# Yukari4_Naninator.net
KiCad netlist of a schematic drawn in EAGLE
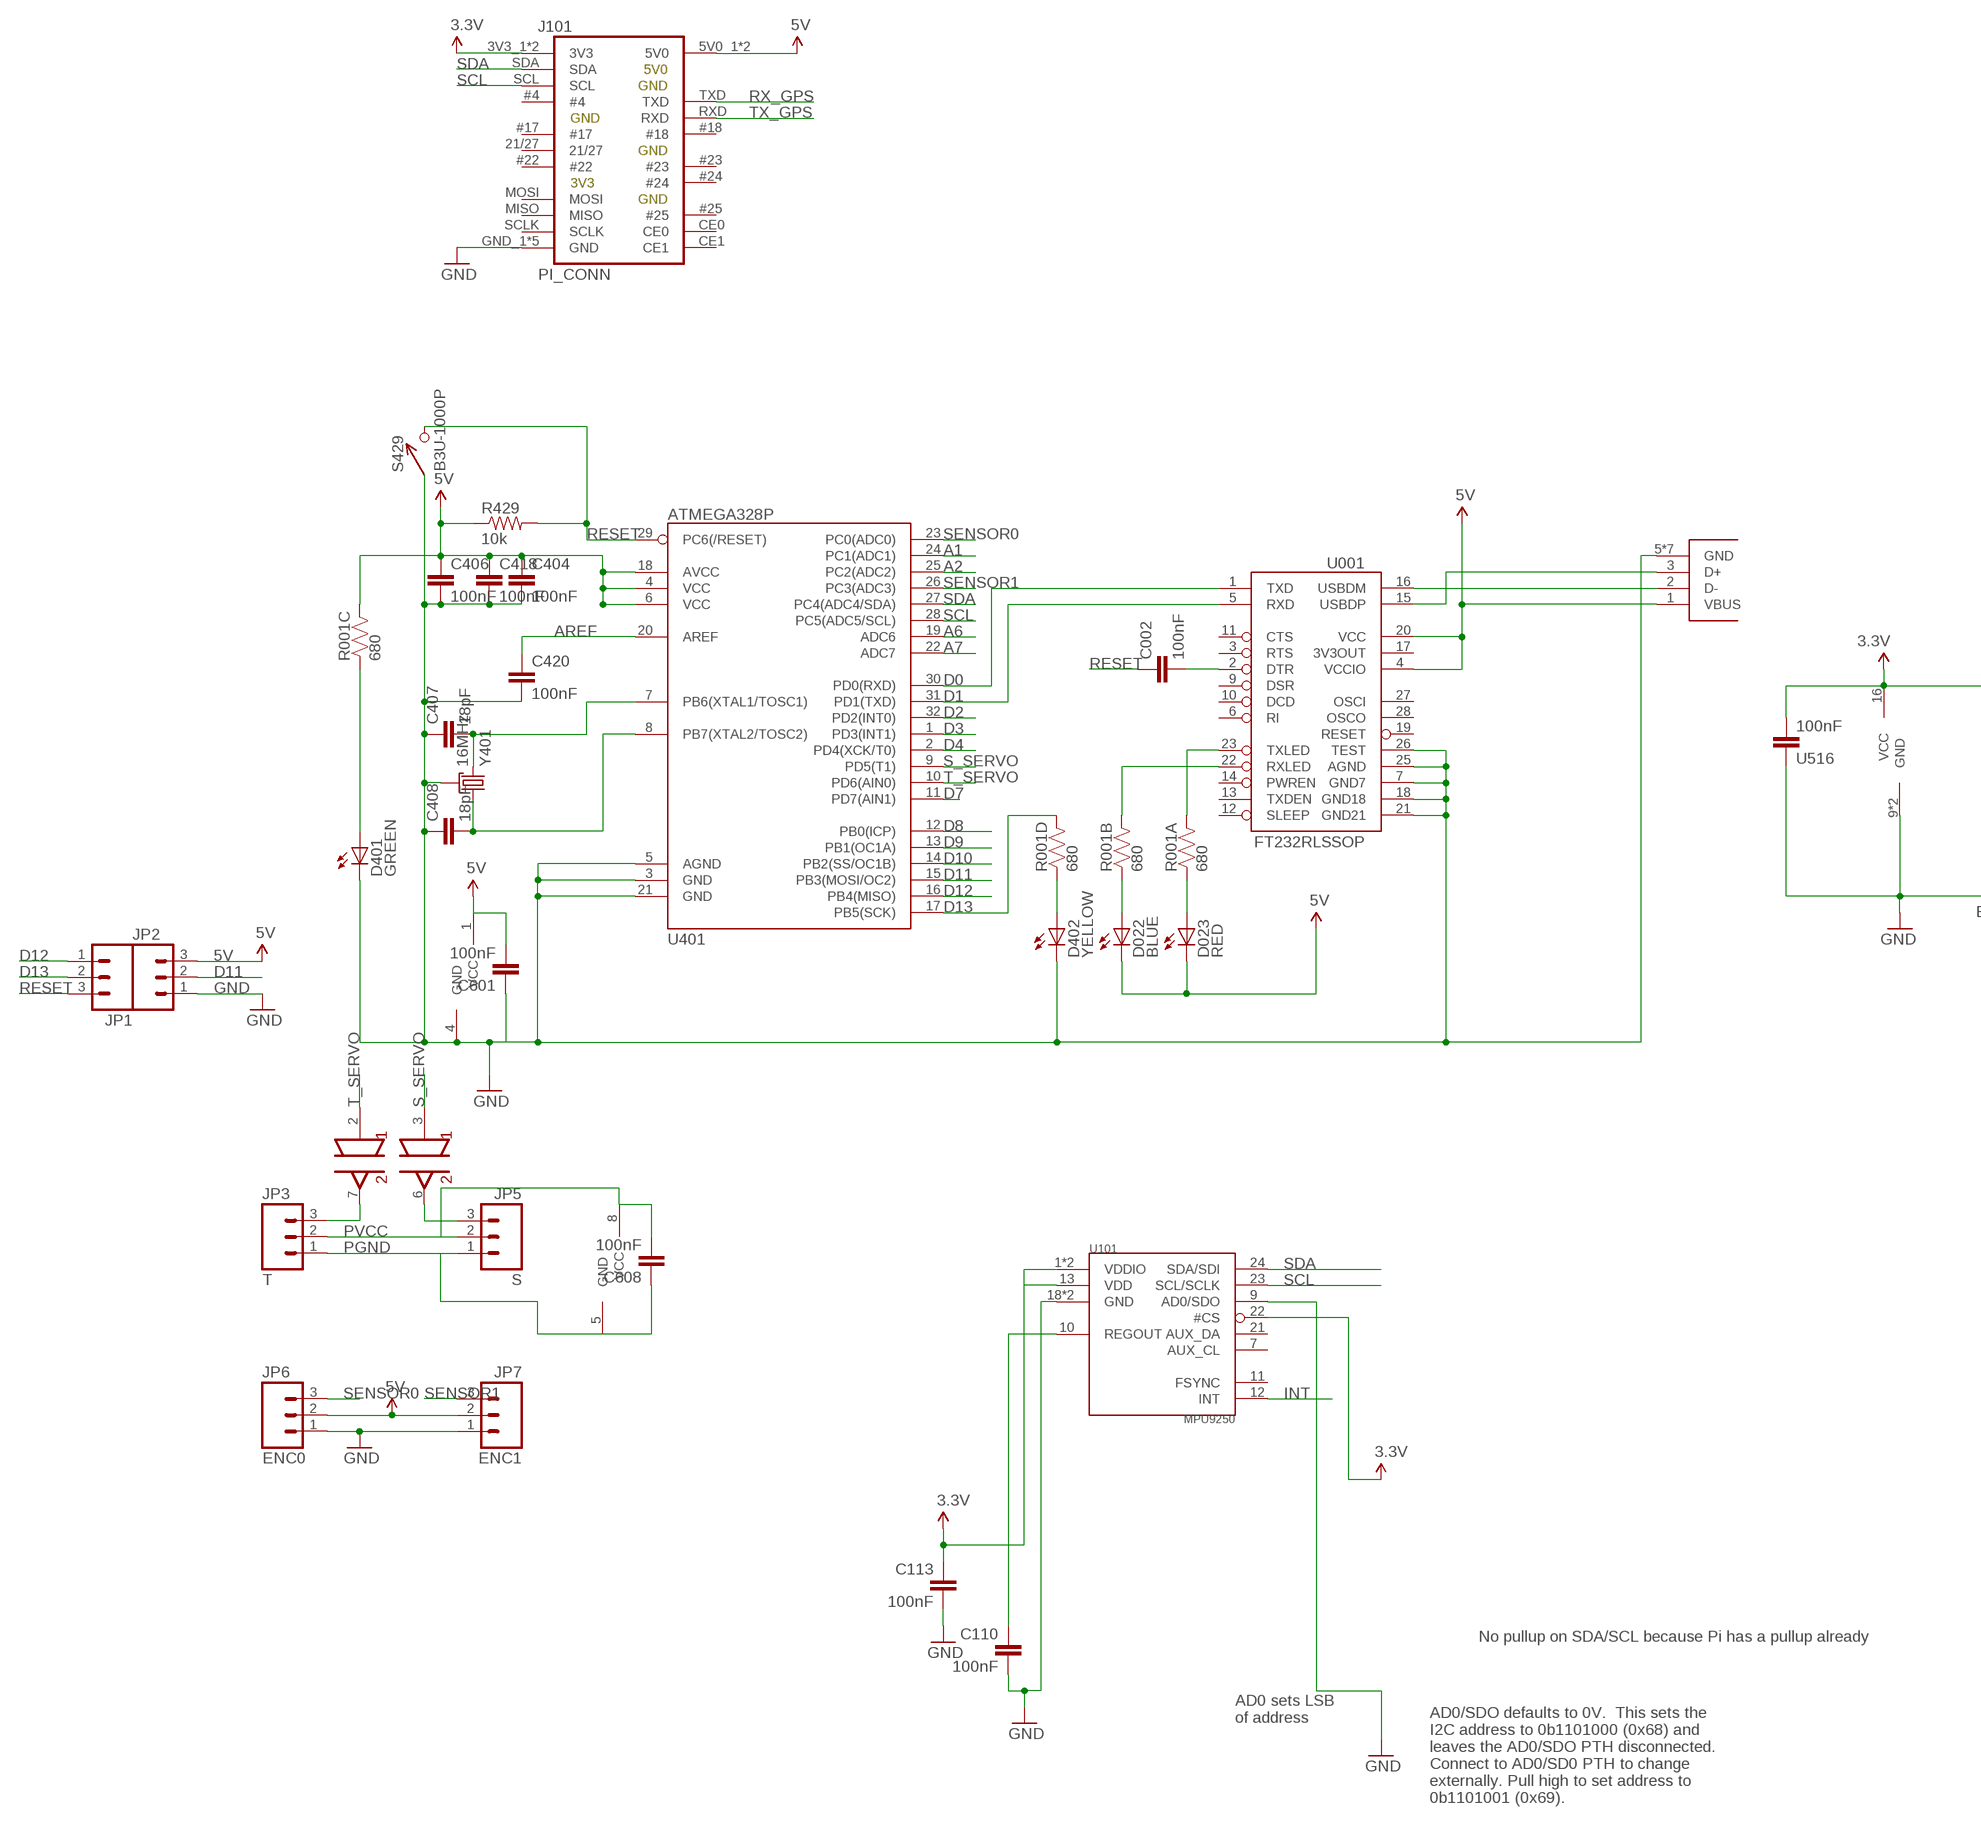
[diagram p0: schematic, sheet 1, part 1 of 2]
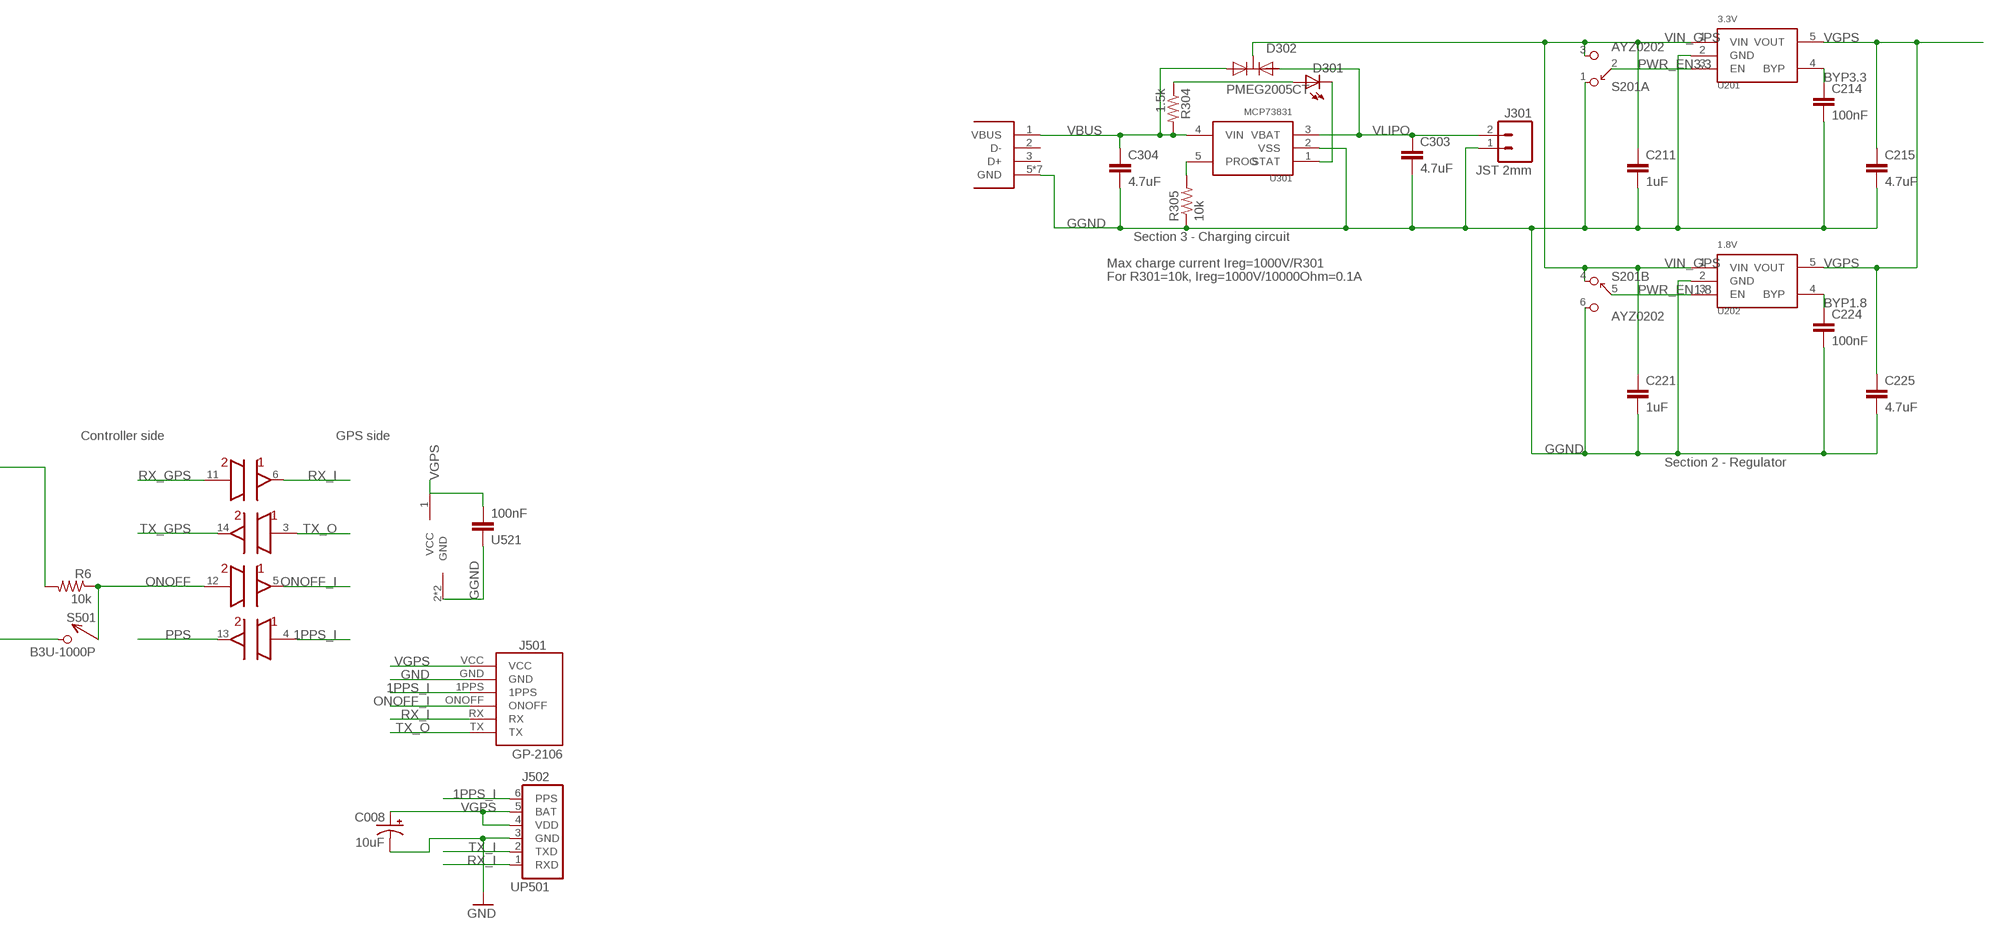
[diagram p1: schematic, sheet 1, part 2 of 2]

(export (version "E")
  (design (tool "Eeschema 10.0.6"))
  (components
    (comp (ref "C002")
      (value "100nF")
      (footprint "eagle-import:0402-CAP")
      (libsource (lib "eagle-import") (part "CAP0402-CAP"))
    )
    (comp (ref "C008")
      (value "10uF")
      (footprint "eagle-import:EIA3216")
      (libsource (lib "eagle-import") (part "CAP_POL1206"))
    )
    (comp (ref "C110")
      (value "100nF")
      (footprint "eagle-import:0402-CAP")
      (libsource (lib "eagle-import") (part "SparkFun-Capacitors_CAP0402-CAP"))
    )
    (comp (ref "C113")
      (value "100nF")
      (footprint "eagle-import:0402-CAP")
      (libsource (lib "eagle-import") (part "SparkFun-Capacitors_CAP0402-CAP"))
    )
    (comp (ref "C211")
      (value "1uF")
      (footprint "eagle-import:0402-CAP")
      (libsource (lib "eagle-import") (part "CAP0402-CAP"))
    )
    (comp (ref "C214")
      (value "100nF")
      (footprint "eagle-import:0402-CAP")
      (libsource (lib "eagle-import") (part "CAP0402-CAP"))
    )
    (comp (ref "C215")
      (value "4.7uF")
      (footprint "eagle-import:0402-CAP")
      (libsource (lib "eagle-import") (part "CAP0402-CAP"))
    )
    (comp (ref "C221")
      (value "1uF")
      (footprint "eagle-import:0402-CAP")
      (libsource (lib "eagle-import") (part "CAP0402-CAP"))
    )
    (comp (ref "C224")
      (value "100nF")
      (footprint "eagle-import:0402-CAP")
      (libsource (lib "eagle-import") (part "CAP0402-CAP"))
    )
    (comp (ref "C225")
      (value "4.7uF")
      (footprint "eagle-import:0402-CAP")
      (libsource (lib "eagle-import") (part "CAP0402-CAP"))
    )
    (comp (ref "C303")
      (value "4.7uF")
      (footprint "eagle-import:0402-CAP")
      (libsource (lib "eagle-import") (part "CAP0402-CAP"))
    )
    (comp (ref "C304")
      (value "4.7uF")
      (footprint "eagle-import:0402-CAP")
      (libsource (lib "eagle-import") (part "CAP0402-CAP"))
    )
    (comp (ref "C404")
      (value "100nF")
      (footprint "eagle-import:0402-CAP")
      (libsource (lib "eagle-import") (part "CAP0402-CAP"))
    )
    (comp (ref "C406")
      (value "100nF")
      (footprint "eagle-import:0402-CAP")
      (libsource (lib "eagle-import") (part "CAP0402-CAP"))
    )
    (comp (ref "C407")
      (value "18pF")
      (footprint "eagle-import:0402-CAP")
      (libsource (lib "eagle-import") (part "CAP0402-CAP"))
    )
    (comp (ref "C408")
      (value "18pF")
      (footprint "eagle-import:0402-CAP")
      (libsource (lib "eagle-import") (part "CAP0402-CAP"))
    )
    (comp (ref "C418")
      (value "100nF")
      (footprint "eagle-import:0402-CAP")
      (libsource (lib "eagle-import") (part "CAP0402-CAP"))
    )
    (comp (ref "C420")
      (value "100nF")
      (footprint "eagle-import:0402-CAP")
      (libsource (lib "eagle-import") (part "CAP0402-CAP"))
    )
    (comp (ref "C601")
      (value "100nF")
      (footprint "eagle-import:0402-CAP")
      (libsource (lib "eagle-import") (part "CAP0402-CAP"))
    )
    (comp (ref "C608")
      (value "100nF")
      (footprint "eagle-import:0402-CAP")
      (libsource (lib "eagle-import") (part "CAP0402-CAP"))
    )
    (comp (ref "D022")
      (value "BLUE")
      (footprint "eagle-import:LED-0603")
      (libsource (lib "eagle-import") (part "SparkFun-LED_LED0603"))
    )
    (comp (ref "D023")
      (value "RED")
      (footprint "eagle-import:LED-0603")
      (libsource (lib "eagle-import") (part "SparkFun-LED_LED0603"))
    )
    (comp (ref "D301")
      (value "YELLOW")
      (footprint "eagle-import:LED-0603")
      (libsource (lib "eagle-import") (part "LED0603"))
    )
    (comp (ref "D302")
      (value "PMEG2005CT")
      (footprint "eagle-import:SOT-23-3")
      (libsource (lib "eagle-import") (part "DIODE_COMMON_CATHODEPMEG2005CT"))
    )
    (comp (ref "D401")
      (value "GREEN")
      (footprint "eagle-import:LED-0603")
      (libsource (lib "eagle-import") (part "SparkFun-LED_LED0603"))
    )
    (comp (ref "D402")
      (value "YELLOW")
      (footprint "eagle-import:LED-0603")
      (libsource (lib "eagle-import") (part "SparkFun-LED_LED0603"))
    )
    (comp (ref "J001")
      (value "USB_MICROB_JST")
      (footprint "eagle-import:UB-MC5BR3-SD204-4S")
      (libsource (lib "eagle-import") (part "USB_MICROB_JST"))
    )
    (comp (ref "J101")
      (value "PI_CONN")
      (footprint "eagle-import:PI_CONN")
      (libsource (lib "eagle-import") (part "PI_CONN"))
    )
    (comp (ref "J301")
      (value "JST 2mm")
      (footprint "eagle-import:JST-2-SMD")
      (libsource (lib "eagle-import") (part "M02-JST-2MM-SMT"))
    )
    (comp (ref "J302")
      (value "USB_MICROB_JST")
      (footprint "eagle-import:UB-MC5BR3-SD204-4S")
      (libsource (lib "eagle-import") (part "USB_MICROB_JST"))
    )
    (comp (ref "J501")
      (value "GP-2106")
      (footprint "eagle-import:GP-2106")
      (libsource (lib "eagle-import") (part "GP-2106"))
    )
    (comp (ref "J502")
      (value "UP501")
      (footprint "eagle-import:UP501")
      (libsource (lib "eagle-import") (part "UP501"))
    )
    (comp (ref "JP1")
      (value "M03PTH")
      (footprint "eagle-import:1X03")
      (libsource (lib "eagle-import") (part "M03PTH"))
    )
    (comp (ref "JP2")
      (value "M03PTH")
      (footprint "eagle-import:1X03")
      (libsource (lib "eagle-import") (part "M03PTH"))
    )
    (comp (ref "JP3")
      (value "T")
      (footprint "eagle-import:1X03")
      (libsource (lib "eagle-import") (part "M03PTH"))
    )
    (comp (ref "JP5")
      (value "S")
      (footprint "eagle-import:1X03")
      (libsource (lib "eagle-import") (part "M03PTH"))
    )
    (comp (ref "JP6")
      (value "ENC0")
      (footprint "eagle-import:1X03")
      (libsource (lib "eagle-import") (part "M03PTH"))
    )
    (comp (ref "JP7")
      (value "ENC1")
      (footprint "eagle-import:1X03")
      (libsource (lib "eagle-import") (part "M03PTH"))
    )
    (comp (ref "R001")
      (value "680")
      (footprint "eagle-import:CRA04")
      (fields (field (name "DIGIKEY") "CRA4S8680CT-ND"))
      (libsource (lib "eagle-import") (part "RP404"))
    )
    (comp (ref "R6")
      (value "10k")
      (footprint "eagle-import:0402-RES")
      (libsource (lib "eagle-import") (part "RESISTOR0402-RES"))
    )
    (comp (ref "R304")
      (value "1.5k")
      (footprint "eagle-import:0402-RES")
      (libsource (lib "eagle-import") (part "RESISTOR0402-RES"))
    )
    (comp (ref "R305")
      (value "10k")
      (footprint "eagle-import:0402-RES")
      (libsource (lib "eagle-import") (part "RESISTOR0402-RES"))
    )
    (comp (ref "R429")
      (value "10k")
      (footprint "eagle-import:0402-RES")
      (libsource (lib "eagle-import") (part "SparkFun-Passives_RESISTOR0402-RES"))
    )
    (comp (ref "S201")
      (value "AYZ0202")
      (footprint "eagle-import:AYZ0202")
      (libsource (lib "eagle-import") (part "AYZ0202"))
    )
    (comp (ref "S429")
      (value "B3U-1000P")
      (footprint "eagle-import:B3U-1000P")
      (libsource (lib "eagle-import") (part "B3U-1000P"))
    )
    (comp (ref "S501")
      (value "B3U-1000P")
      (footprint "eagle-import:B3U-1000P")
      (libsource (lib "eagle-import") (part "B3U-1000P"))
    )
    (comp (ref "U001")
      (value "FT232RLSSOP")
      (footprint "eagle-import:SSOP28DB")
      (libsource (lib "eagle-import") (part "FT232RLSSOP"))
    )
    (comp (ref "U101")
      (value "MPU9250")
      (footprint "eagle-import:LQFN_3MM_3MM")
      (libsource (lib "eagle-import") (part "MPU9250"))
    )
    (comp (ref "U201")
      (value "3.3V")
      (footprint "eagle-import:SOT-23-5")
      (libsource (lib "eagle-import") (part "MIC5319D5"))
    )
    (comp (ref "U202")
      (value "1.8V")
      (footprint "eagle-import:SOT-23-5")
      (libsource (lib "eagle-import") (part "MIC5319D5"))
    )
    (comp (ref "U301")
      (value "MCP73831")
      (footprint "eagle-import:SOT-23-5")
      (libsource (lib "eagle-import") (part "MCP73831"))
    )
    (comp (ref "U401")
      (value "ATMEGA328P")
      (footprint "eagle-import:TQFP32-08")
      (libsource (lib "eagle-import") (part "ATMEGA168"))
    )
    (comp (ref "U501")
      (value "ADUM242E")
      (footprint "eagle-import:16-SOIC-W")
      (libsource (lib "eagle-import") (part "ADUM242E"))
    )
    (comp (ref "U516")
      (value "100nF")
      (footprint "eagle-import:0402-CAP")
      (libsource (lib "eagle-import") (part "CAP0402-CAP"))
    )
    (comp (ref "U521")
      (value "100nF")
      (footprint "eagle-import:0402-CAP")
      (libsource (lib "eagle-import") (part "CAP0402-CAP"))
    )
    (comp (ref "U601")
      (value "ADUM3221")
      (footprint "eagle-import:SO8N")
      (libsource (lib "eagle-import") (part "ADUM3221"))
    )
    (comp (ref "Y401")
      (value "16MHz")
      (footprint "eagle-import:CRYSTAL_SMD_2MM_2_5MM")
      (libsource (lib "eagle-import") (part "CX2520"))
    )
  )
  (nets
    (net (code "1") (name "/1PPS_I") (class "Default")
      (node (ref "J501") (pin "1PPS") (pinfunction "1PPS_1PPS") (pintype "bidirectional"))
      (node (ref "J502") (pin "6") (pinfunction "PPS_6") (pintype "passive"))
      (node (ref "U501") (pin "4") (pinfunction "IN_4") (pintype "input"))
    )
    (net (code "2") (name "/A1") (class "Default")
      (node (ref "U401") (pin "24") (pinfunction "PC1(ADC1)_24") (pintype "bidirectional"))
    )
    (net (code "3") (name "/A2") (class "Default")
      (node (ref "U401") (pin "25") (pinfunction "PC2(ADC2)_25") (pintype "bidirectional"))
    )
    (net (code "4") (name "/A6") (class "Default")
      (node (ref "U401") (pin "19") (pinfunction "ADC6_19") (pintype "bidirectional"))
    )
    (net (code "5") (name "/A7") (class "Default")
      (node (ref "U401") (pin "22") (pinfunction "ADC7_22") (pintype "bidirectional"))
    )
    (net (code "6") (name "/AREF") (class "Default")
      (node (ref "C420") (pin "1") (pinfunction "1_1") (pintype "passive"))
      (node (ref "U401") (pin "20") (pinfunction "AREF_20") (pintype "bidirectional"))
    )
    (net (code "7") (name "/BYP1.8") (class "Default")
      (node (ref "C224") (pin "1") (pinfunction "1_1") (pintype "passive"))
      (node (ref "U202") (pin "4") (pinfunction "BYP_4") (pintype "bidirectional"))
    )
    (net (code "8") (name "/BYP3.3") (class "Default")
      (node (ref "C214") (pin "1") (pinfunction "1_1") (pintype "passive"))
      (node (ref "U201") (pin "4") (pinfunction "BYP_4") (pintype "bidirectional"))
    )
    (net (code "9") (name "/D0") (class "Default")
      (node (ref "U001") (pin "1") (pinfunction "TXD_1") (pintype "output"))
      (node (ref "U401") (pin "30") (pinfunction "PD0(RXD)_30") (pintype "bidirectional"))
    )
    (net (code "10") (name "/D1") (class "Default")
      (node (ref "U001") (pin "5") (pinfunction "RXD_5") (pintype "input"))
      (node (ref "U401") (pin "31") (pinfunction "PD1(TXD)_31") (pintype "bidirectional"))
    )
    (net (code "11") (name "/D2") (class "Default")
      (node (ref "U401") (pin "32") (pinfunction "PD2(INT0)_32") (pintype "bidirectional"))
    )
    (net (code "12") (name "/D3") (class "Default")
      (node (ref "U401") (pin "1") (pinfunction "PD3(INT1)_1") (pintype "bidirectional"))
    )
    (net (code "13") (name "/D4") (class "Default")
      (node (ref "U401") (pin "2") (pinfunction "PD4(XCK/T0)_2") (pintype "bidirectional"))
    )
    (net (code "14") (name "/D7") (class "Default")
      (node (ref "U401") (pin "11") (pinfunction "PD7(AIN1)_11") (pintype "bidirectional"))
    )
    (net (code "15") (name "/D8") (class "Default")
      (node (ref "U401") (pin "12") (pinfunction "PB0(ICP)_12") (pintype "bidirectional"))
    )
    (net (code "16") (name "/D9") (class "Default")
      (node (ref "U401") (pin "13") (pinfunction "PB1(OC1A)_13") (pintype "bidirectional"))
    )
    (net (code "17") (name "/D10") (class "Default")
      (node (ref "U401") (pin "14") (pinfunction "PB2(SS/OC1B)_14") (pintype "bidirectional"))
    )
    (net (code "18") (name "/D11") (class "Default")
      (node (ref "JP2") (pin "2") (pinfunction "2_2") (pintype "passive"))
      (node (ref "U401") (pin "15") (pinfunction "PB3(MOSI/OC2)_15") (pintype "bidirectional"))
    )
    (net (code "19") (name "/D12") (class "Default")
      (node (ref "JP1") (pin "1") (pinfunction "1_1") (pintype "passive"))
      (node (ref "U401") (pin "16") (pinfunction "PB4(MISO)_16") (pintype "bidirectional"))
    )
    (net (code "20") (name "/D13") (class "Default")
      (node (ref "JP1") (pin "2") (pinfunction "2_2") (pintype "passive"))
      (node (ref "R001") (pin "5") (pinfunction "2_5") (pintype "passive"))
      (node (ref "U401") (pin "17") (pinfunction "PB5(SCK)_17") (pintype "bidirectional"))
    )
    (net (code "21") (name "/GGND") (class "Default")
      (node (ref "C211") (pin "2") (pinfunction "2_2") (pintype "passive"))
      (node (ref "C214") (pin "2") (pinfunction "2_2") (pintype "passive"))
      (node (ref "C215") (pin "2") (pinfunction "2_2") (pintype "passive"))
      (node (ref "C221") (pin "2") (pinfunction "2_2") (pintype "passive"))
      (node (ref "C224") (pin "2") (pinfunction "2_2") (pintype "passive"))
      (node (ref "C225") (pin "2") (pinfunction "2_2") (pintype "passive"))
      (node (ref "C303") (pin "2") (pinfunction "2_2") (pintype "passive"))
      (node (ref "C304") (pin "2") (pinfunction "2_2") (pintype "passive"))
      (node (ref "J301") (pin "1") (pinfunction "1_1") (pintype "passive"))
      (node (ref "J302") (pin "5") (pinfunction "GND_5") (pintype "bidirectional"))
      (node (ref "J302") (pin "P$10") (pinfunction "GND_P$10") (pintype "bidirectional"))
      (node (ref "J302") (pin "P$11") (pinfunction "GND_P$11") (pintype "bidirectional"))
      (node (ref "J302") (pin "P$6") (pinfunction "GND_P$6") (pintype "bidirectional"))
      (node (ref "J302") (pin "P$7") (pinfunction "GND_P$7") (pintype "bidirectional"))
      (node (ref "J302") (pin "P$8") (pinfunction "GND_P$8") (pintype "bidirectional"))
      (node (ref "J302") (pin "P$9") (pinfunction "GND_P$9") (pintype "bidirectional"))
      (node (ref "R305") (pin "1") (pinfunction "1_1") (pintype "passive"))
      (node (ref "S201") (pin "1") (pinfunction "P$1_1") (pintype "bidirectional"))
      (node (ref "S201") (pin "6") (pinfunction "P$2_6") (pintype "bidirectional"))
      (node (ref "U201") (pin "2") (pinfunction "GND_2") (pintype "bidirectional"))
      (node (ref "U202") (pin "2") (pinfunction "GND_2") (pintype "bidirectional"))
      (node (ref "U301") (pin "2") (pinfunction "VSS_2") (pintype "power_in"))
      (node (ref "U501") (pin "2") (pinfunction "GND_2") (pintype "bidirectional"))
      (node (ref "U501") (pin "8") (pinfunction "GND_8") (pintype "bidirectional"))
      (node (ref "U521") (pin "1") (pinfunction "1_1") (pintype "passive"))
    )
    (net (code "22") (name "/INT") (class "Default")
      (node (ref "U101") (pin "12") (pinfunction "INT_12") (pintype "bidirectional"))
    )
    (net (code "23") (name "/ONOFF") (class "Default")
      (node (ref "R6") (pin "1") (pinfunction "1_1") (pintype "passive"))
      (node (ref "S501") (pin "P$1") (pinfunction "1_P$1") (pintype "bidirectional"))
      (node (ref "U501") (pin "12") (pinfunction "IN_12") (pintype "input"))
    )
    (net (code "24") (name "/ONOFF_I") (class "Default")
      (node (ref "J501") (pin "ONOFF") (pinfunction "ONOFF_ONOFF") (pintype "bidirectional"))
      (node (ref "U501") (pin "5") (pinfunction "OUT_5") (pintype "bidirectional"))
    )
    (net (code "25") (name "/PGND") (class "Default")
      (node (ref "C608") (pin "1") (pinfunction "1_1") (pintype "passive"))
      (node (ref "JP3") (pin "1") (pinfunction "1_1") (pintype "passive"))
      (node (ref "JP5") (pin "1") (pinfunction "1_1") (pintype "passive"))
      (node (ref "U601") (pin "5") (pinfunction "GND_5") (pintype "bidirectional"))
    )
    (net (code "26") (name "/PPS") (class "Default")
      (node (ref "U501") (pin "13") (pinfunction "OUT_13") (pintype "bidirectional"))
    )
    (net (code "27") (name "/PVCC") (class "Default")
      (node (ref "C608") (pin "2") (pinfunction "2_2") (pintype "passive"))
      (node (ref "JP3") (pin "2") (pinfunction "2_2") (pintype "passive"))
      (node (ref "JP5") (pin "2") (pinfunction "2_2") (pintype "passive"))
      (node (ref "U601") (pin "8") (pinfunction "VCC_8") (pintype "bidirectional"))
    )
    (net (code "28") (name "/PWR_EN1.8") (class "Default")
      (node (ref "S201") (pin "5") (pinfunction "P$3_5") (pintype "bidirectional"))
      (node (ref "U202") (pin "3") (pinfunction "EN_3") (pintype "bidirectional"))
    )
    (net (code "29") (name "/PWR_EN3.3") (class "Default")
      (node (ref "S201") (pin "2") (pinfunction "P$3_2") (pintype "bidirectional"))
      (node (ref "U201") (pin "3") (pinfunction "EN_3") (pintype "bidirectional"))
    )
    (net (code "30") (name "/RESET") (class "Default")
      (node (ref "C002") (pin "1") (pinfunction "1_1") (pintype "passive"))
      (node (ref "JP1") (pin "3") (pinfunction "3_3") (pintype "passive"))
      (node (ref "R429") (pin "2") (pinfunction "2_2") (pintype "passive"))
      (node (ref "S429") (pin "P$2") (pinfunction "2_P$2") (pintype "bidirectional"))
      (node (ref "U401") (pin "29") (pinfunction "PC6(/RESET)_29") (pintype "bidirectional"))
    )
    (net (code "31") (name "/RX_GPS") (class "Default")
      (node (ref "J101") (pin "TXD") (pinfunction "TXD_TXD") (pintype "passive"))
      (node (ref "U501") (pin "11") (pinfunction "IN_11") (pintype "input"))
    )
    (net (code "32") (name "/RX_I") (class "Default")
      (node (ref "J501") (pin "RX") (pinfunction "RX_RX") (pintype "bidirectional"))
      (node (ref "J502") (pin "1") (pinfunction "RXD_1") (pintype "passive"))
      (node (ref "U501") (pin "6") (pinfunction "OUT_6") (pintype "bidirectional"))
    )
    (net (code "33") (name "/SCL") (class "Default")
      (node (ref "J101") (pin "SCL") (pinfunction "SCL_SCL") (pintype "passive"))
      (node (ref "U101") (pin "23") (pinfunction "SCL/SCLK_23") (pintype "bidirectional"))
      (node (ref "U401") (pin "28") (pinfunction "PC5(ADC5/SCL)_28") (pintype "bidirectional"))
    )
    (net (code "34") (name "/SDA") (class "Default")
      (node (ref "J101") (pin "SDA") (pinfunction "SDA_SDA") (pintype "passive"))
      (node (ref "U101") (pin "24") (pinfunction "SDA/SDI_24") (pintype "bidirectional"))
      (node (ref "U401") (pin "27") (pinfunction "PC4(ADC4/SDA)_27") (pintype "bidirectional"))
    )
    (net (code "35") (name "/SENSOR0") (class "Default")
      (node (ref "JP6") (pin "3") (pinfunction "3_3") (pintype "passive"))
      (node (ref "U401") (pin "23") (pinfunction "PC0(ADC0)_23") (pintype "bidirectional"))
    )
    (net (code "36") (name "/SENSOR1") (class "Default")
      (node (ref "JP7") (pin "3") (pinfunction "3_3") (pintype "passive"))
      (node (ref "U401") (pin "26") (pinfunction "PC3(ADC3)_26") (pintype "bidirectional"))
    )
    (net (code "37") (name "/S_SERVO") (class "Default")
      (node (ref "U401") (pin "9") (pinfunction "PD5(T1)_9") (pintype "bidirectional"))
      (node (ref "U601") (pin "3") (pinfunction "IN_3") (pintype "input"))
    )
    (net (code "38") (name "/TX_GPS") (class "Default")
      (node (ref "J101") (pin "RXD") (pinfunction "RXD_RXD") (pintype "passive"))
      (node (ref "U501") (pin "14") (pinfunction "OUT_14") (pintype "bidirectional"))
    )
    (net (code "39") (name "/TX_I") (class "Default")
      (node (ref "J502") (pin "2") (pinfunction "TXD_2") (pintype "passive"))
    )
    (net (code "40") (name "/TX_O") (class "Default")
      (node (ref "J501") (pin "TX") (pinfunction "TX_TX") (pintype "bidirectional"))
      (node (ref "U501") (pin "3") (pinfunction "IN_3") (pintype "input"))
    )
    (net (code "41") (name "/T_SERVO") (class "Default")
      (node (ref "U401") (pin "10") (pinfunction "PD6(AIN0)_10") (pintype "bidirectional"))
      (node (ref "U601") (pin "2") (pinfunction "IN_2") (pintype "input"))
    )
    (net (code "42") (name "/VBUS") (class "Default")
      (node (ref "C304") (pin "1") (pinfunction "1_1") (pintype "passive"))
      (node (ref "D302") (pin "1") (pinfunction "A1_1") (pintype "passive"))
      (node (ref "J302") (pin "1") (pinfunction "VBUS_1") (pintype "bidirectional"))
      (node (ref "R304") (pin "2") (pinfunction "2_2") (pintype "passive"))
      (node (ref "U301") (pin "4") (pinfunction "VIN_4") (pintype "power_in"))
    )
    (net (code "43") (name "/VGPS") (class "Default")
      (node (ref "C008") (pin "A") (pinfunction "+_A") (pintype "passive"))
      (node (ref "C215") (pin "1") (pinfunction "1_1") (pintype "passive"))
      (node (ref "C225") (pin "1") (pinfunction "1_1") (pintype "passive"))
      (node (ref "J501") (pin "VCC") (pinfunction "VCC_VCC") (pintype "bidirectional"))
      (node (ref "J502") (pin "4") (pinfunction "VDD_4") (pintype "passive"))
      (node (ref "J502") (pin "5") (pinfunction "BAT_5") (pintype "passive"))
      (node (ref "U201") (pin "5") (pinfunction "VOUT_5") (pintype "bidirectional"))
      (node (ref "U202") (pin "5") (pinfunction "VOUT_5") (pintype "bidirectional"))
      (node (ref "U501") (pin "1") (pinfunction "VCC_1") (pintype "bidirectional"))
      (node (ref "U521") (pin "2") (pinfunction "2_2") (pintype "passive"))
    )
    (net (code "44") (name "/VIN_GPS") (class "Default")
      (node (ref "C211") (pin "1") (pinfunction "1_1") (pintype "passive"))
      (node (ref "C221") (pin "1") (pinfunction "1_1") (pintype "passive"))
      (node (ref "D302") (pin "3") (pinfunction "K_3") (pintype "passive"))
      (node (ref "S201") (pin "3") (pinfunction "P$2_3") (pintype "bidirectional"))
      (node (ref "S201") (pin "4") (pinfunction "P$1_4") (pintype "bidirectional"))
      (node (ref "U201") (pin "1") (pinfunction "VIN_1") (pintype "bidirectional"))
      (node (ref "U202") (pin "1") (pinfunction "VIN_1") (pintype "bidirectional"))
    )
    (net (code "45") (name "/VLIPO") (class "Default")
      (node (ref "C303") (pin "1") (pinfunction "1_1") (pintype "passive"))
      (node (ref "D302") (pin "2") (pinfunction "A2_2") (pintype "passive"))
      (node (ref "J301") (pin "2") (pinfunction "2_2") (pintype "passive"))
      (node (ref "U301") (pin "3") (pinfunction "VBAT_3") (pintype "power_in"))
    )
    (net (code "46") (name "3.3V") (class "Default")
      (node (ref "C113") (pin "1") (pinfunction "1_1") (pintype "passive"))
      (node (ref "J101") (pin "3V3_1") (pinfunction "3V3_3V3_1") (pintype "passive"))
      (node (ref "J101") (pin "3V3_2") (pinfunction "3V3_3V3_2") (pintype "passive"))
      (node (ref "R6") (pin "2") (pinfunction "2_2") (pintype "passive"))
      (node (ref "U101") (pin "1") (pinfunction "VDDIO_1") (pintype "bidirectional"))
      (node (ref "U101") (pin "13") (pinfunction "VDD_13") (pintype "bidirectional"))
      (node (ref "U101") (pin "22") (pinfunction "#CS_22") (pintype "bidirectional"))
      (node (ref "U101") (pin "8") (pinfunction "VDDIO_8") (pintype "bidirectional"))
      (node (ref "U501") (pin "16") (pinfunction "VCC_16") (pintype "bidirectional"))
      (node (ref "U516") (pin "2") (pinfunction "2_2") (pintype "passive"))
    )
    (net (code "47") (name "5V") (class "Default")
      (node (ref "C404") (pin "1") (pinfunction "1_1") (pintype "passive"))
      (node (ref "C406") (pin "1") (pinfunction "1_1") (pintype "passive"))
      (node (ref "C418") (pin "1") (pinfunction "1_1") (pintype "passive"))
      (node (ref "C601") (pin "2") (pinfunction "2_2") (pintype "passive"))
      (node (ref "D022") (pin "C") (pinfunction "C_C") (pintype "passive"))
      (node (ref "D023") (pin "C") (pinfunction "C_C") (pintype "passive"))
      (node (ref "J001") (pin "1") (pinfunction "VBUS_1") (pintype "bidirectional"))
      (node (ref "J101") (pin "5V0_1") (pinfunction "5V0_5V0_1") (pintype "passive"))
      (node (ref "J101") (pin "5V0_2") (pinfunction "5V0_5V0_2") (pintype "passive"))
      (node (ref "JP2") (pin "3") (pinfunction "3_3") (pintype "passive"))
      (node (ref "JP6") (pin "2") (pinfunction "2_2") (pintype "passive"))
      (node (ref "JP7") (pin "2") (pinfunction "2_2") (pintype "passive"))
      (node (ref "R001") (pin "6") (pinfunction "2_6") (pintype "passive"))
      (node (ref "R429") (pin "1") (pinfunction "1_1") (pintype "passive"))
      (node (ref "U001") (pin "20") (pinfunction "VCC_20") (pintype "power_in"))
      (node (ref "U001") (pin "4") (pinfunction "VCCIO_4") (pintype "power_in"))
      (node (ref "U401") (pin "18") (pinfunction "AVCC_18") (pintype "bidirectional"))
      (node (ref "U401") (pin "4") (pinfunction "VCC_4") (pintype "bidirectional"))
      (node (ref "U401") (pin "6") (pinfunction "VCC_6") (pintype "bidirectional"))
      (node (ref "U601") (pin "1") (pinfunction "VCC_1") (pintype "bidirectional"))
    )
    (net (code "48") (name "GND") (class "Default")
      (node (ref "C008") (pin "C") (pinfunction "-_C") (pintype "passive"))
      (node (ref "C110") (pin "2") (pinfunction "2_2") (pintype "passive"))
      (node (ref "C113") (pin "2") (pinfunction "2_2") (pintype "passive"))
      (node (ref "C404") (pin "2") (pinfunction "2_2") (pintype "passive"))
      (node (ref "C406") (pin "2") (pinfunction "2_2") (pintype "passive"))
      (node (ref "C407") (pin "1") (pinfunction "1_1") (pintype "passive"))
      (node (ref "C408") (pin "1") (pinfunction "1_1") (pintype "passive"))
      (node (ref "C418") (pin "2") (pinfunction "2_2") (pintype "passive"))
      (node (ref "C420") (pin "2") (pinfunction "2_2") (pintype "passive"))
      (node (ref "C601") (pin "1") (pinfunction "1_1") (pintype "passive"))
      (node (ref "D401") (pin "C") (pinfunction "C_C") (pintype "passive"))
      (node (ref "D402") (pin "C") (pinfunction "C_C") (pintype "passive"))
      (node (ref "J001") (pin "5") (pinfunction "GND_5") (pintype "bidirectional"))
      (node (ref "J001") (pin "P$10") (pinfunction "GND_P$10") (pintype "bidirectional"))
      (node (ref "J001") (pin "P$11") (pinfunction "GND_P$11") (pintype "bidirectional"))
      (node (ref "J001") (pin "P$6") (pinfunction "GND_P$6") (pintype "bidirectional"))
      (node (ref "J001") (pin "P$7") (pinfunction "GND_P$7") (pintype "bidirectional"))
      (node (ref "J001") (pin "P$8") (pinfunction "GND_P$8") (pintype "bidirectional"))
      (node (ref "J001") (pin "P$9") (pinfunction "GND_P$9") (pintype "bidirectional"))
      (node (ref "J101") (pin "GND_1") (pinfunction "GND_GND_1") (pintype "passive"))
      (node (ref "J101") (pin "GND_2") (pinfunction "GND_GND_2") (pintype "passive"))
      (node (ref "J101") (pin "GND_3") (pinfunction "GND_GND_3") (pintype "passive"))
      (node (ref "J101") (pin "GND_4") (pinfunction "GND_GND_4") (pintype "passive"))
      (node (ref "J101") (pin "GND_5") (pinfunction "GND_GND_5") (pintype "passive"))
      (node (ref "J501") (pin "GND") (pinfunction "GND_GND") (pintype "bidirectional"))
      (node (ref "J502") (pin "3") (pinfunction "GND_3") (pintype "passive"))
      (node (ref "JP2") (pin "1") (pinfunction "1_1") (pintype "passive"))
      (node (ref "JP6") (pin "1") (pinfunction "1_1") (pintype "passive"))
      (node (ref "JP7") (pin "1") (pinfunction "1_1") (pintype "passive"))
      (node (ref "S429") (pin "P$1") (pinfunction "1_P$1") (pintype "bidirectional"))
      (node (ref "S501") (pin "P$2") (pinfunction "2_P$2") (pintype "bidirectional"))
      (node (ref "U001") (pin "18") (pinfunction "GND18_18") (pintype "power_in"))
      (node (ref "U001") (pin "21") (pinfunction "GND21_21") (pintype "power_in"))
      (node (ref "U001") (pin "25") (pinfunction "AGND_25") (pintype "power_in"))
      (node (ref "U001") (pin "26") (pinfunction "TEST_26") (pintype "input"))
      (node (ref "U001") (pin "7") (pinfunction "GND7_7") (pintype "power_in"))
      (node (ref "U101") (pin "18") (pinfunction "GND_18") (pintype "bidirectional"))
      (node (ref "U101") (pin "20") (pinfunction "GND_20") (pintype "bidirectional"))
      (node (ref "U101") (pin "9") (pinfunction "AD0/SDO_9") (pintype "bidirectional"))
      (node (ref "U401") (pin "21") (pinfunction "GND_21") (pintype "bidirectional"))
      (node (ref "U401") (pin "3") (pinfunction "GND_3") (pintype "bidirectional"))
      (node (ref "U401") (pin "5") (pinfunction "AGND_5") (pintype "bidirectional"))
      (node (ref "U501") (pin "15") (pinfunction "GND_15") (pintype "bidirectional"))
      (node (ref "U501") (pin "9") (pinfunction "GND_9") (pintype "bidirectional"))
      (node (ref "U516") (pin "1") (pinfunction "1_1") (pintype "passive"))
      (node (ref "U601") (pin "4") (pinfunction "GND_4") (pintype "bidirectional"))
      (node (ref "Y401") (pin "2") (pinfunction "GND_2") (pintype "passive"))
      (node (ref "Y401") (pin "4") (pinfunction "GND_4") (pintype "passive"))
    )
    (net (code "49") (name "Net-(D023-PadA)") (class "Default")
      (node (ref "D023") (pin "A") (pinfunction "A_A") (pintype "passive"))
      (node (ref "R001") (pin "1") (pinfunction "1_1") (pintype "passive"))
    )
    (net (code "50") (name "Net-(D301-PadA)") (class "Default")
      (node (ref "D301") (pin "A") (pinfunction "A_A") (pintype "passive"))
      (node (ref "R304") (pin "1") (pinfunction "1_1") (pintype "passive"))
    )
    (net (code "51") (name "Net-(J001-D+)") (class "Default")
      (node (ref "J001") (pin "3") (pinfunction "D+_3") (pintype "bidirectional"))
      (node (ref "U001") (pin "15") (pinfunction "USBDP_15") (pintype "bidirectional"))
    )
    (net (code "52") (name "Net-(J001-D-)") (class "Default")
      (node (ref "J001") (pin "2") (pinfunction "D-_2") (pintype "bidirectional"))
      (node (ref "U001") (pin "16") (pinfunction "USBDM_16") (pintype "bidirectional"))
    )
    (net (code "53") (name "Net-(R001A-2)") (class "Default")
      (node (ref "R001") (pin "8") (pinfunction "2_8") (pintype "passive"))
      (node (ref "U001") (pin "23") (pinfunction "TXLED_23") (pintype "input"))
    )
    (net (code "54") (name "Net-(R001B-1)") (class "Default")
      (node (ref "D022") (pin "A") (pinfunction "A_A") (pintype "passive"))
      (node (ref "R001") (pin "2") (pinfunction "1_2") (pintype "passive"))
    )
    (net (code "55") (name "Net-(R001B-2)") (class "Default")
      (node (ref "R001") (pin "7") (pinfunction "2_7") (pintype "passive"))
      (node (ref "U001") (pin "22") (pinfunction "RXLED_22") (pintype "input"))
    )
    (net (code "56") (name "Net-(R001C-1)") (class "Default")
      (node (ref "D401") (pin "A") (pinfunction "A_A") (pintype "passive"))
      (node (ref "R001") (pin "3") (pinfunction "1_3") (pintype "passive"))
    )
    (net (code "57") (name "Net-(R001D-1)") (class "Default")
      (node (ref "D402") (pin "A") (pinfunction "A_A") (pintype "passive"))
      (node (ref "R001") (pin "4") (pinfunction "1_4") (pintype "passive"))
    )
    (net (code "58") (name "Net-(U001-DTR)") (class "Default")
      (node (ref "C002") (pin "2") (pinfunction "2_2") (pintype "passive"))
      (node (ref "U001") (pin "2") (pinfunction "DTR_2") (pintype "output"))
    )
    (net (code "59") (name "Net-(U101-REGOUT)") (class "Default")
      (node (ref "C110") (pin "1") (pinfunction "1_1") (pintype "passive"))
      (node (ref "U101") (pin "10") (pinfunction "REGOUT_10") (pintype "bidirectional"))
    )
    (net (code "60") (name "Net-(U301-PROG)") (class "Default")
      (node (ref "R305") (pin "2") (pinfunction "2_2") (pintype "passive"))
      (node (ref "U301") (pin "5") (pinfunction "PROG_5") (pintype "passive"))
    )
    (net (code "61") (name "Net-(U301-STAT)") (class "Default")
      (node (ref "D301") (pin "C") (pinfunction "C_C") (pintype "passive"))
      (node (ref "U301") (pin "1") (pinfunction "STAT_1") (pintype "bidirectional"))
    )
    (net (code "62") (name "Net-(U401-PB6(XTAL1{slash}TOSC1))") (class "Default")
      (node (ref "C407") (pin "2") (pinfunction "2_2") (pintype "passive"))
      (node (ref "U401") (pin "7") (pinfunction "PB6(XTAL1/TOSC1)_7") (pintype "bidirectional"))
      (node (ref "Y401") (pin "3") (pinfunction "2_3") (pintype "passive"))
    )
    (net (code "63") (name "Net-(U401-PB7(XTAL2{slash}TOSC2))") (class "Default")
      (node (ref "C408") (pin "2") (pinfunction "2_2") (pintype "passive"))
      (node (ref "U401") (pin "8") (pinfunction "PB7(XTAL2/TOSC2)_8") (pintype "bidirectional"))
      (node (ref "Y401") (pin "1") (pinfunction "1_1") (pintype "passive"))
    )
    (net (code "64") (name "Net-(U601A-OUT)") (class "Default")
      (node (ref "JP3") (pin "3") (pinfunction "3_3") (pintype "passive"))
      (node (ref "U601") (pin "7") (pinfunction "OUT_7") (pintype "bidirectional"))
    )
    (net (code "65") (name "Net-(U601B-OUT)") (class "Default")
      (node (ref "JP5") (pin "3") (pinfunction "3_3") (pintype "passive"))
      (node (ref "U601") (pin "6") (pinfunction "OUT_6") (pintype "bidirectional"))
    )
    (net (code "66") (name "unconnected-(J101-Pad#4)") (class "Default")
      (node (ref "J101") (pin "#4") (pinfunction "#4_#4") (pintype "passive"))
    )
    (net (code "67") (name "unconnected-(J101-Pad#17)") (class "Default")
      (node (ref "J101") (pin "#17") (pinfunction "#17_#17") (pintype "passive"))
    )
    (net (code "68") (name "unconnected-(J101-Pad#18)") (class "Default")
      (node (ref "J101") (pin "#18") (pinfunction "#18_#18") (pintype "passive"))
    )
    (net (code "69") (name "unconnected-(J101-Pad#22)") (class "Default")
      (node (ref "J101") (pin "#22") (pinfunction "#22_#22") (pintype "passive"))
    )
    (net (code "70") (name "unconnected-(J101-Pad#23)") (class "Default")
      (node (ref "J101") (pin "#23") (pinfunction "#23_#23") (pintype "passive"))
    )
    (net (code "71") (name "unconnected-(J101-Pad#24)") (class "Default")
      (node (ref "J101") (pin "#24") (pinfunction "#24_#24") (pintype "passive"))
    )
    (net (code "72") (name "unconnected-(J101-Pad#25)") (class "Default")
      (node (ref "J101") (pin "#25") (pinfunction "#25_#25") (pintype "passive"))
    )
    (net (code "73") (name "unconnected-(J101-Pad21{slash}27)") (class "Default")
      (node (ref "J101") (pin "21/27") (pinfunction "21/27_21/27") (pintype "passive"))
    )
    (net (code "74") (name "unconnected-(J101-PadCE0)") (class "Default")
      (node (ref "J101") (pin "CE0") (pinfunction "CE0_CE0") (pintype "passive"))
    )
    (net (code "75") (name "unconnected-(J101-PadCE1)") (class "Default")
      (node (ref "J101") (pin "CE1") (pinfunction "CE1_CE1") (pintype "passive"))
    )
    (net (code "76") (name "unconnected-(J101-PadMISO)") (class "Default")
      (node (ref "J101") (pin "MISO") (pinfunction "MISO_MISO") (pintype "passive"))
    )
    (net (code "77") (name "unconnected-(J101-PadMOSI)") (class "Default")
      (node (ref "J101") (pin "MOSI") (pinfunction "MOSI_MOSI") (pintype "passive"))
    )
    (net (code "78") (name "unconnected-(J101-PadSCLK)") (class "Default")
      (node (ref "J101") (pin "SCLK") (pinfunction "SCLK_SCLK") (pintype "passive"))
    )
    (net (code "79") (name "unconnected-(J302-D+-Pad3)") (class "Default")
      (node (ref "J302") (pin "3") (pinfunction "D+_3") (pintype "bidirectional"))
    )
    (net (code "80") (name "unconnected-(J302-D--Pad2)") (class "Default")
      (node (ref "J302") (pin "2") (pinfunction "D-_2") (pintype "bidirectional"))
    )
    (net (code "81") (name "unconnected-(U001-3V3OUT-Pad17)") (class "Default")
      (node (ref "U001") (pin "17") (pinfunction "3V3OUT_17") (pintype "output"))
    )
    (net (code "82") (name "unconnected-(U001-CTS-Pad11)") (class "Default")
      (node (ref "U001") (pin "11") (pinfunction "CTS_11") (pintype "input"))
    )
    (net (code "83") (name "unconnected-(U001-DCD-Pad10)") (class "Default")
      (node (ref "U001") (pin "10") (pinfunction "DCD_10") (pintype "input"))
    )
    (net (code "84") (name "unconnected-(U001-DSR-Pad9)") (class "Default")
      (node (ref "U001") (pin "9") (pinfunction "DSR_9") (pintype "input"))
    )
    (net (code "85") (name "unconnected-(U001-OSCI-Pad27)") (class "Default")
      (node (ref "U001") (pin "27") (pinfunction "OSCI_27") (pintype "input"))
    )
    (net (code "86") (name "unconnected-(U001-OSCO-Pad28)") (class "Default")
      (node (ref "U001") (pin "28") (pinfunction "OSCO_28") (pintype "output"))
    )
    (net (code "87") (name "unconnected-(U001-PWREN-Pad14)") (class "Default")
      (node (ref "U001") (pin "14") (pinfunction "PWREN_14") (pintype "input"))
    )
    (net (code "88") (name "unconnected-(U001-RESET-Pad19)") (class "Default")
      (node (ref "U001") (pin "19") (pinfunction "RESET_19") (pintype "input"))
    )
    (net (code "89") (name "unconnected-(U001-RI-Pad6)") (class "Default")
      (node (ref "U001") (pin "6") (pinfunction "RI_6") (pintype "input"))
    )
    (net (code "90") (name "unconnected-(U001-RTS-Pad3)") (class "Default")
      (node (ref "U001") (pin "3") (pinfunction "RTS_3") (pintype "output"))
    )
    (net (code "91") (name "unconnected-(U001-SLEEP-Pad12)") (class "Default")
      (node (ref "U001") (pin "12") (pinfunction "SLEEP_12") (pintype "input"))
    )
    (net (code "92") (name "unconnected-(U001-TXDEN-Pad13)") (class "Default")
      (node (ref "U001") (pin "13") (pinfunction "TXDEN_13") (pintype "input"))
    )
    (net (code "93") (name "unconnected-(U101-AUX_CL-Pad7)") (class "Default")
      (node (ref "U101") (pin "7") (pinfunction "AUX_CL_7") (pintype "bidirectional"))
    )
    (net (code "94") (name "unconnected-(U101-AUX_DA-Pad21)") (class "Default")
      (node (ref "U101") (pin "21") (pinfunction "AUX_DA_21") (pintype "bidirectional"))
    )
    (net (code "95") (name "unconnected-(U101-FSYNC-Pad11)") (class "Default")
      (node (ref "U101") (pin "11") (pinfunction "FSYNC_11") (pintype "bidirectional"))
    )
  )
)
